# AnalogConnector.net
KiCad netlist of a schematic drawn in Altium Designer
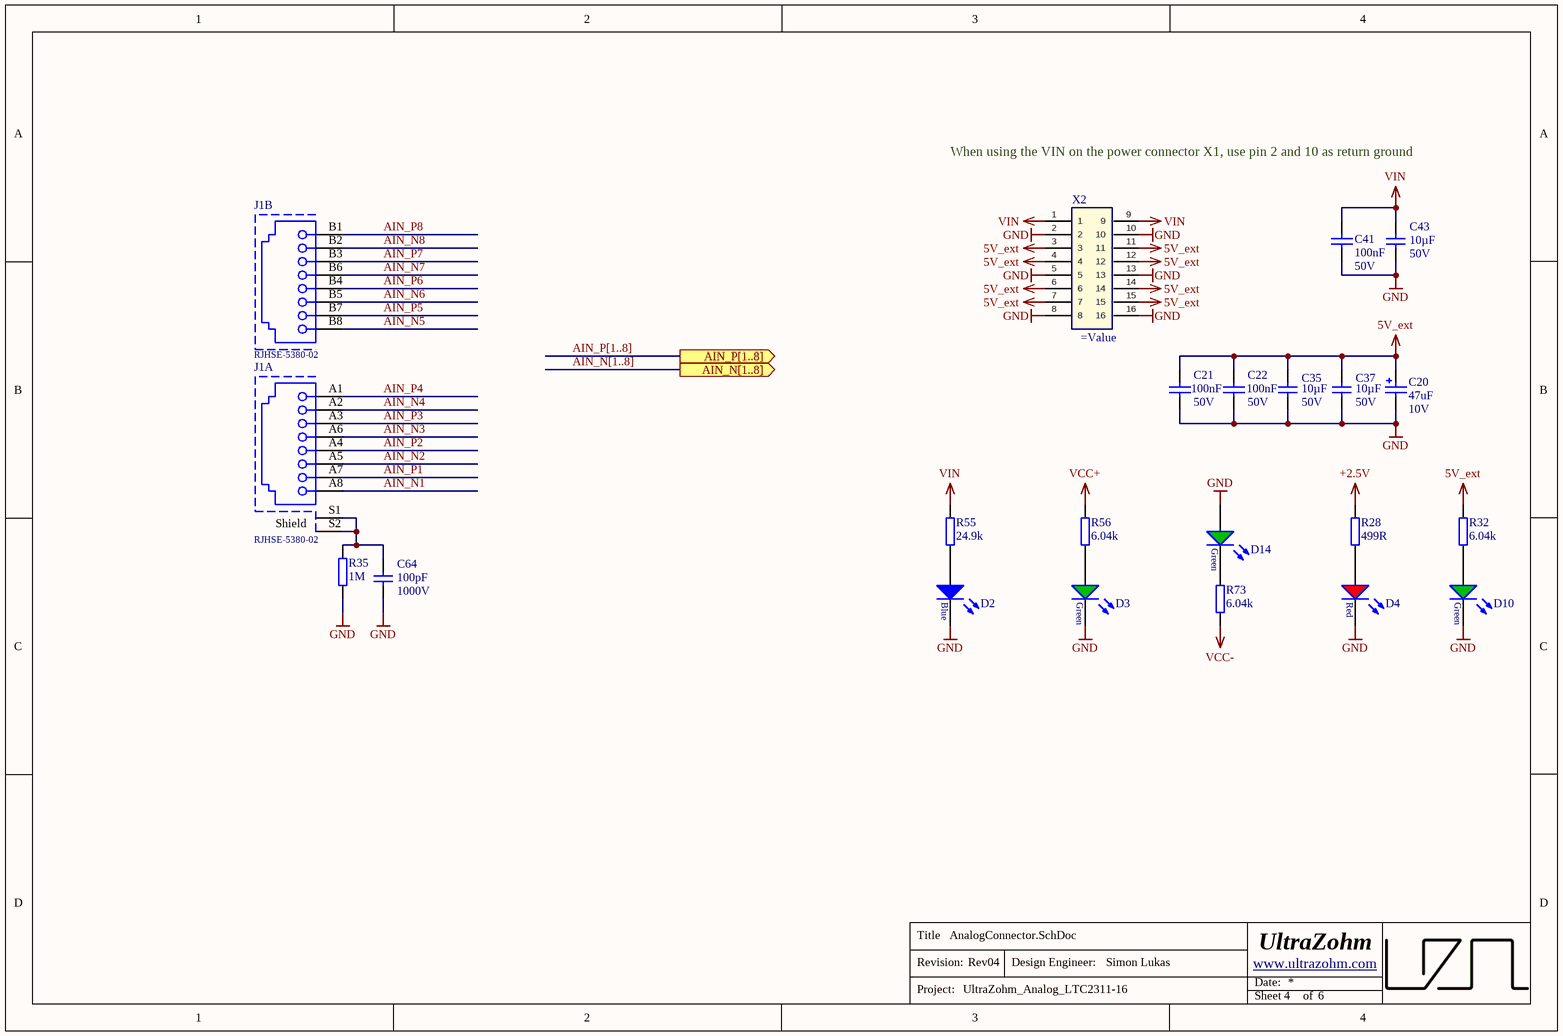
[diagram p0: AnalogConnector.SchDoc]

(export (version "E")
  (design (tool "Eeschema 10.0.6"))
  (components
    (comp (ref "C20")
      (value "47uF")
      (footprint "WCAP-ASLI_5x5.5")
      (description "WCAP-ASLI Aluminum Electrolytic Capacitor, V-Chip, SMT, D5xH5.5mm, 47uF, 10V")
      (fields
        (field (name "MPN") "865080242004")
        (field (name "MF") "Wurth Elektronik")
        (field (name "VOLTAGE") "10V")
      )
      (libsource (lib "UltraZohm_ADC") (part "865080142007"))
    )
    (comp (ref "C21")
      (value "100nF")
      (footprint "CAPC1608X07N")
      (fields
        (field (name "MF") "Yageo")
        (field (name "MPN") "CC0603KRX7R9BB104")
        (field (name "VOLTAGE") "50V")
      )
      (libsource (lib "UltraZohm_ADC") (part "Cap_0603"))
    )
    (comp (ref "C22")
      (value "100nF")
      (footprint "CAPC1608X07N")
      (fields
        (field (name "MF") "Yageo")
        (field (name "MPN") "CC0603KRX7R9BB104")
        (field (name "VOLTAGE") "50V")
      )
      (libsource (lib "UltraZohm_ADC") (part "Cap_0603"))
    )
    (comp (ref "C35")
      (value "10µF")
      (footprint "C_1206")
      (description "Capacitor 1206")
      (fields
        (field (name "TOLERANCE") "10%")
        (field (name "MF") "Samsung")
        (field (name "VOLTAGE") "50V")
        (field (name "CREATED") "2020_09_17_Liegmann")
      )
      (libsource (lib "UltraZohm_ADC") (part "C_1206"))
    )
    (comp (ref "C37")
      (value "10µF")
      (footprint "C_1206")
      (description "Capacitor 1206")
      (fields
        (field (name "TOLERANCE") "10%")
        (field (name "MF") "Samsung")
        (field (name "VOLTAGE") "50V")
        (field (name "CREATED") "2020_09_17_Liegmann")
      )
      (libsource (lib "UltraZohm_ADC") (part "C_1206"))
    )
    (comp (ref "C41")
      (value "100nF")
      (footprint "CAPC1608X07N")
      (fields
        (field (name "MF") "Yageo")
        (field (name "MPN") "CC0603KRX7R9BB104")
        (field (name "VOLTAGE") "50V")
        (field (name "TOLERANCE") "10%")
      )
      (libsource (lib "UltraZohm_ADC") (part "Cap_0603"))
    )
    (comp (ref "C43")
      (value "10µF")
      (footprint "C_1206")
      (description "Capacitor 1206")
      (fields (field (name "TOLERANCE") "20%") (field (name "MF") "Samsung") (field (name "VOLTAGE") "50V"))
      (libsource (lib "UltraZohm_ADC") (part "C_1206"))
    )
    (comp (ref "C64")
      (value "100pF")
      (footprint "C_1206")
      (description "Capacitor 1206")
      (fields
        (field (name "TOLERANCE") "5%")
        (field (name "MF") "Würth Elektronik")
        (field (name "VOLTAGE") "1000V")
        (field (name "CREATED") "2018_06_25_AGeiger")
      )
      (libsource (lib "UltraZohm_ADC") (part "C_1206"))
    )
    (comp (ref "D2")
      (value "150060BS75000")
      (footprint "WL-SMCW_0603")
      (description "WL-SMCW SMD Mono-color Chip LED Waterclear, size 0603, Blue, 3.2 V, 140°")
      (fields (field (name "MF") "Wuerth Elektronik") (field (name "CREATED") "2018_09_06_AGeiger"))
      (libsource (lib "UltraZohm_ADC") (part "LED_Blue_0603"))
    )
    (comp (ref "D3")
      (value "150060GS75000")
      (footprint "WL-SMCW_0603")
      (description "WL-SMCW SMD Mono-color Chip LED Waterclear, size 0603, Green, 3.2 V, 140°")
      (fields (field (name "MF") "Wuerth Elektronik") (field (name "CREATED") "2018_09_06_AGeiger"))
      (libsource (lib "UltraZohm_ADC") (part "LED_Green_0603"))
    )
    (comp (ref "D4")
      (value "150060RS75000")
      (footprint "WL-SMCW_0603")
      (description "WL-SMCW SMD Mono-color Chip LED Waterclear, size 0603, Red, 2 V, 140°")
      (fields (field (name "MF") "Wuerth Elektronik") (field (name "CREATED") "2018_09_06_AGeiger"))
      (libsource (lib "UltraZohm_ADC") (part "LED_Red_0603"))
    )
    (comp (ref "D10")
      (value "150060GS75000")
      (footprint "WL-SMCW_0603")
      (description "WL-SMCW SMD Mono-color Chip LED Waterclear, size 0603, Green, 3.2 V, 140°")
      (fields (field (name "MF") "Wuerth Elektronik") (field (name "CREATED") "2018_09_06_AGeiger"))
      (libsource (lib "UltraZohm_ADC") (part "LED_Green_0603"))
    )
    (comp (ref "D14")
      (value "150060GS75000")
      (footprint "WL-SMCW_0603")
      (description "WL-SMCW SMD Mono-color Chip LED Waterclear, size 0603, Green, 3.2 V, 140°")
      (fields (field (name "MF") "Wuerth Elektronik") (field (name "CREATED") "2018_09_06_AGeiger"))
      (libsource (lib "UltraZohm_ADC") (part "LED_Green_0603"))
    )
    (comp (ref "J1")
      (value "RJHSE-5380-02")
      (footprint "RJHSE-5380-02")
      (description "Modular Connectors / Ethernet Connectors CAT 5 MODULAR JACK HIGH TEMP")
      (fields (field (name "MF") "Amphenol"))
      (libsource (lib "UltraZohm_ADC") (part "RJHSE-5380-02"))
    )
    (comp (ref "R28")
      (value "499R")
      (footprint "RESC1608X06N")
      (fields (field (name "MF") "Vishay / Dale") (field (name "MPN") "CRCW0603499RFKEAC"))
      (libsource (lib "UltraZohm_ADC") (part "R_0603"))
    )
    (comp (ref "R32")
      (value "6.04k")
      (footprint "RESC1608X06N")
      (fields (field (name "MF") "Vishay / Dale") (field (name "MPN") "RCS06036K04FKEA"))
      (libsource (lib "UltraZohm_ADC") (part "R_0603"))
    )
    (comp (ref "R35")
      (value "1M")
      (footprint "RESC1608X06N")
      (fields
        (field (name "MF") "Vishay / Dale")
        (field (name "MPN") "CRCW06031M00FKEAC")
        (field (name "TOLERANCE") "1%")
      )
      (libsource (lib "UltraZohm_ADC") (part "R_0603"))
    )
    (comp (ref "R55")
      (value "24.9k")
      (footprint "RESC1608X06N")
      (fields (field (name "MF") "Vishay / Dale") (field (name "MPN") "CRCW060324K9FKEAC"))
      (libsource (lib "UltraZohm_ADC") (part "R_0603"))
    )
    (comp (ref "R56")
      (value "6.04k")
      (footprint "RESC1608X06N")
      (fields (field (name "MF") "Vishay / Dale") (field (name "MPN") "RCS06036K04FKEA"))
      (libsource (lib "UltraZohm_ADC") (part "R_0603"))
    )
    (comp (ref "R73")
      (value "6.04k")
      (footprint "RESC1608X06N")
      (fields (field (name "MF") "Vishay / Dale") (field (name "MPN") "RCS06036K04FKEA"))
      (libsource (lib "UltraZohm_ADC") (part "R_0603"))
    )
    (comp (ref "X2")
      (value "~")
      (footprint "IPL1-108-01-L-D-RA-K")
      (description "2.54mm Double Row Terminal Assembly")
      (fields
        (field (name "MF") "SAMTEC")
        (field (name "MPN") "IPL1-108-01-L-D-RA-K")
        (field (name "CREATED") "2018_09_17_AGeiger")
      )
      (libsource (lib "UltraZohm_ADC") (part "IPL1-108-XX-X-D-X"))
    )
  )
  (nets
    (net (code "1") (name "+2.5V") (class "Default") (node (ref "R28") (pin "2") (pintype "passive")))
    (net (code "2") (name "/AIN_N1") (class "Default")
      (node (ref "J1") (pin "A8") (pinfunction "A8_A8") (pintype "passive"))
    )
    (net (code "3") (name "/AIN_N2") (class "Default")
      (node (ref "J1") (pin "A5") (pinfunction "A5_A5") (pintype "passive"))
    )
    (net (code "4") (name "/AIN_N3") (class "Default")
      (node (ref "J1") (pin "A6") (pinfunction "A6_A6") (pintype "passive"))
    )
    (net (code "5") (name "/AIN_N4") (class "Default")
      (node (ref "J1") (pin "A2") (pinfunction "A2_A2") (pintype "passive"))
    )
    (net (code "6") (name "/AIN_N5") (class "Default")
      (node (ref "J1") (pin "B8") (pinfunction "B8_B8") (pintype "passive"))
    )
    (net (code "7") (name "/AIN_N6") (class "Default")
      (node (ref "J1") (pin "B5") (pinfunction "B5_B5") (pintype "passive"))
    )
    (net (code "8") (name "/AIN_N7") (class "Default")
      (node (ref "J1") (pin "B6") (pinfunction "B6_B6") (pintype "passive"))
    )
    (net (code "9") (name "/AIN_N8") (class "Default")
      (node (ref "J1") (pin "B2") (pinfunction "B2_B2") (pintype "passive"))
    )
    (net (code "11") (name "/AIN_P1") (class "Default")
      (node (ref "J1") (pin "A7") (pinfunction "A7_A7") (pintype "passive"))
    )
    (net (code "12") (name "/AIN_P2") (class "Default")
      (node (ref "J1") (pin "A4") (pinfunction "A4_A4") (pintype "passive"))
    )
    (net (code "13") (name "/AIN_P3") (class "Default")
      (node (ref "J1") (pin "A3") (pinfunction "A3_A3") (pintype "passive"))
    )
    (net (code "14") (name "/AIN_P4") (class "Default")
      (node (ref "J1") (pin "A1") (pinfunction "A1_A1") (pintype "passive"))
    )
    (net (code "15") (name "/AIN_P5") (class "Default")
      (node (ref "J1") (pin "B7") (pinfunction "B7_B7") (pintype "passive"))
    )
    (net (code "16") (name "/AIN_P6") (class "Default")
      (node (ref "J1") (pin "B4") (pinfunction "B4_B4") (pintype "passive"))
    )
    (net (code "17") (name "/AIN_P7") (class "Default")
      (node (ref "J1") (pin "B3") (pinfunction "B3_B3") (pintype "passive"))
    )
    (net (code "18") (name "/AIN_P8") (class "Default")
      (node (ref "J1") (pin "B1") (pinfunction "B1_B1") (pintype "passive"))
    )
    (net (code "20") (name "5V_ext") (class "Default")
      (node (ref "C20") (pin "2") (pinfunction "P_2") (pintype "passive"))
      (node (ref "C21") (pin "2") (pinfunction "2_2") (pintype "passive"))
      (node (ref "C22") (pin "2") (pinfunction "2_2") (pintype "passive"))
      (node (ref "C35") (pin "2") (pinfunction "2_2") (pintype "passive"))
      (node (ref "C37") (pin "2") (pinfunction "2_2") (pintype "passive"))
      (node (ref "R32") (pin "2") (pintype "passive"))
      (node (ref "X2") (pin "11") (pinfunction "11_11") (pintype "passive"))
      (node (ref "X2") (pin "12") (pinfunction "12_12") (pintype "passive"))
      (node (ref "X2") (pin "14") (pinfunction "14_14") (pintype "passive"))
      (node (ref "X2") (pin "15") (pinfunction "15_15") (pintype "passive"))
      (node (ref "X2") (pin "3") (pinfunction "3_3") (pintype "passive"))
      (node (ref "X2") (pin "4") (pinfunction "4_4") (pintype "passive"))
      (node (ref "X2") (pin "6") (pinfunction "6_6") (pintype "passive"))
      (node (ref "X2") (pin "7") (pinfunction "7_7") (pintype "passive"))
    )
    (net (code "21") (name "GND") (class "Default")
      (node (ref "C20") (pin "1") (pinfunction "N_1") (pintype "passive"))
      (node (ref "C21") (pin "1") (pinfunction "1_1") (pintype "passive"))
      (node (ref "C22") (pin "1") (pinfunction "1_1") (pintype "passive"))
      (node (ref "C35") (pin "1") (pinfunction "1_1") (pintype "passive"))
      (node (ref "C37") (pin "1") (pinfunction "1_1") (pintype "passive"))
      (node (ref "C41") (pin "1") (pinfunction "1_1") (pintype "passive"))
      (node (ref "C43") (pin "1") (pinfunction "1_1") (pintype "passive"))
      (node (ref "C64") (pin "1") (pinfunction "1_1") (pintype "passive"))
      (node (ref "D10") (pin "1") (pinfunction "K_1") (pintype "passive"))
      (node (ref "D14") (pin "2") (pinfunction "A_2") (pintype "passive"))
      (node (ref "D2") (pin "1") (pinfunction "K_1") (pintype "passive"))
      (node (ref "D3") (pin "1") (pinfunction "K_1") (pintype "passive"))
      (node (ref "D4") (pin "1") (pinfunction "K_1") (pintype "passive"))
      (node (ref "R35") (pin "1") (pintype "passive"))
      (node (ref "X2") (pin "10") (pinfunction "10_10") (pintype "passive"))
      (node (ref "X2") (pin "13") (pinfunction "13_13") (pintype "passive"))
      (node (ref "X2") (pin "16") (pinfunction "16_16") (pintype "passive"))
      (node (ref "X2") (pin "2") (pinfunction "2_2") (pintype "passive"))
      (node (ref "X2") (pin "5") (pinfunction "5_5") (pintype "passive"))
      (node (ref "X2") (pin "8") (pinfunction "8_8") (pintype "passive"))
    )
    (net (code "22") (name "Net-(C64-Pad2)") (class "Default")
      (node (ref "C64") (pin "2") (pinfunction "2_2") (pintype "passive"))
      (node (ref "J1") (pin "S1") (pinfunction "S1_S1") (pintype "passive"))
      (node (ref "J1") (pin "S2") (pinfunction "S2_S2") (pintype "passive"))
      (node (ref "R35") (pin "2") (pintype "passive"))
    )
    (net (code "23") (name "Net-(D2-A)") (class "Default")
      (node (ref "D2") (pin "2") (pinfunction "A_2") (pintype "passive"))
      (node (ref "R55") (pin "1") (pintype "passive"))
    )
    (net (code "24") (name "Net-(D3-A)") (class "Default")
      (node (ref "D3") (pin "2") (pinfunction "A_2") (pintype "passive"))
      (node (ref "R56") (pin "1") (pintype "passive"))
    )
    (net (code "25") (name "Net-(D4-A)") (class "Default")
      (node (ref "D4") (pin "2") (pinfunction "A_2") (pintype "passive"))
      (node (ref "R28") (pin "1") (pintype "passive"))
    )
    (net (code "26") (name "Net-(D10-A)") (class "Default")
      (node (ref "D10") (pin "2") (pinfunction "A_2") (pintype "passive"))
      (node (ref "R32") (pin "1") (pintype "passive"))
    )
    (net (code "27") (name "Net-(D14-K)") (class "Default")
      (node (ref "D14") (pin "1") (pinfunction "K_1") (pintype "passive"))
      (node (ref "R73") (pin "2") (pintype "passive"))
    )
    (net (code "28") (name "VCC+") (class "Default") (node (ref "R56") (pin "2") (pintype "passive")))
    (net (code "29") (name "VCC-") (class "Default") (node (ref "R73") (pin "1") (pintype "passive")))
    (net (code "30") (name "VIN") (class "Default")
      (node (ref "C41") (pin "2") (pinfunction "2_2") (pintype "passive"))
      (node (ref "C43") (pin "2") (pinfunction "2_2") (pintype "passive"))
      (node (ref "R55") (pin "2") (pintype "passive"))
      (node (ref "X2") (pin "1") (pinfunction "1_1") (pintype "passive"))
      (node (ref "X2") (pin "9") (pinfunction "9_9") (pintype "passive"))
    )
  )
)
